# CDRon_wifi.net
KiCad netlist of a schematic drawn in Altium Designer
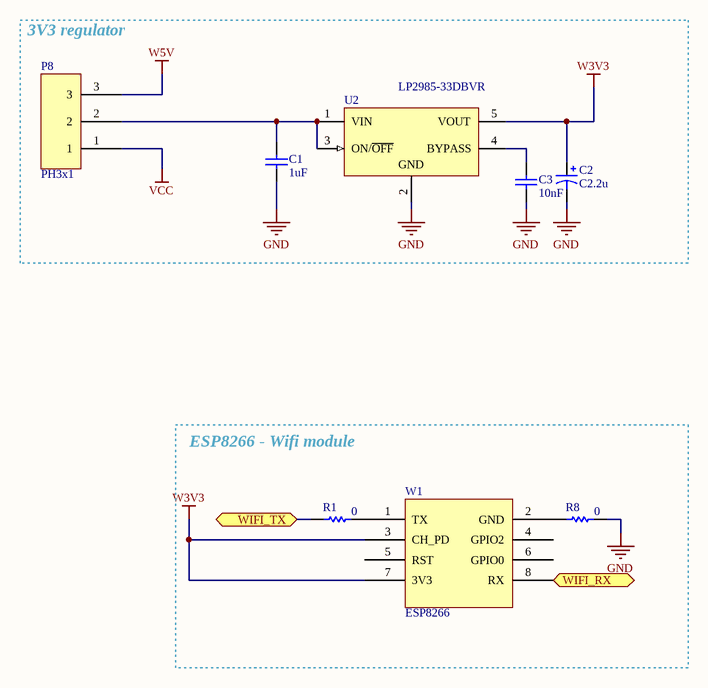
[diagram p0: CDRon_wifi.SchDoc]

(export (version "E")
  (design (tool "Eeschema 10.0.6"))
  (components
    (comp (ref "C1")
      (value "1uF")
      (footprint "0805")
      (description "Cap ceramic")
      (fields (field (name "Comment") "C1u"))
      (libsource (lib "CDRon_lib") (part "C"))
    )
    (comp (ref "C2")
      (value "C2.2u")
      (footprint "Tantalum")
      (description "Tantalum capacitor")
      (libsource (lib "CDRon_lib") (part "C Tantalum"))
    )
    (comp (ref "C3")
      (value "10nF")
      (footprint "C 1206")
      (description "Cap ceramic")
      (fields (field (name "Comment") "C10n"))
      (libsource (lib "CDRon_lib") (part "C"))
    )
    (comp (ref "P8") (value "PH3x1") (footprint "PH3x1") (libsource (lib "CDRon_lib") (part "PH3x1")))
    (comp (ref "R1")
      (value "0")
      (footprint "R 1206")
      (description "Resistencia")
      (fields (field (name ".CREATOR") "SR"))
      (libsource (lib "CDRon_lib") (part "R"))
    )
    (comp (ref "R8")
      (value "0")
      (footprint "R 1206")
      (description "Resistencia")
      (fields (field (name ".CREATOR") "SR"))
      (libsource (lib "CDRon_lib") (part "R"))
    )
    (comp (ref "U2")
      (value "LP2985-33DBVR")
      (footprint "TI-DBV5_N")
      (fields (field (name "MANUFACTURER") "Texas Instruments"))
      (libsource (lib "TI Power Management Linear Regulator Single Channel LDO (0-350mA)") (part "LP2985-10DBVR"))
    )
    (comp (ref "W1") (value "ESP8266") (footprint "ESP8266") (libsource (lib "CDRon_lib") (part "ESP8266")))
  )
  (nets
    (net (code "1") (name "/WIFI_RX") (class "Default")
      (node (ref "W1") (pin "8") (pinfunction "RX_8") (pintype "passive"))
    )
    (net (code "2") (name "/WIFI_TX") (class "Default")
      (node (ref "R1") (pin "1") (pinfunction "1_1") (pintype "passive"))
    )
    (net (code "3") (name "GND") (class "Default")
      (node (ref "C1") (pin "1") (pinfunction "1_1") (pintype "passive"))
      (node (ref "C2") (pin "2") (pinfunction "2_2") (pintype "passive"))
      (node (ref "C3") (pin "1") (pinfunction "1_1") (pintype "passive"))
      (node (ref "R8") (pin "2") (pinfunction "2_2") (pintype "passive"))
      (node (ref "U2") (pin "2") (pinfunction "GND_2") (pintype "power_in"))
    )
    (net (code "4") (name "Net-(U2-BYPASS)") (class "Default")
      (node (ref "C3") (pin "2") (pinfunction "2_2") (pintype "passive"))
      (node (ref "U2") (pin "4") (pinfunction "BYPASS_4") (pintype "passive"))
    )
    (net (code "5") (name "Net-(U2-ON{slash}~{OFF})") (class "Default")
      (node (ref "C1") (pin "2") (pinfunction "2_2") (pintype "passive"))
      (node (ref "P8") (pin "2") (pinfunction "2_2") (pintype "passive"))
      (node (ref "U2") (pin "1") (pinfunction "VIN_1") (pintype "power_in"))
      (node (ref "U2") (pin "3") (pinfunction "ON/~{OFF}_3") (pintype "input"))
    )
    (net (code "6") (name "Net-(W1-GND)") (class "Default")
      (node (ref "R8") (pin "1") (pinfunction "1_1") (pintype "passive"))
      (node (ref "W1") (pin "2") (pinfunction "GND_2") (pintype "passive"))
    )
    (net (code "7") (name "Net-(W1-TX)") (class "Default")
      (node (ref "R1") (pin "2") (pinfunction "2_2") (pintype "passive"))
      (node (ref "W1") (pin "1") (pinfunction "TX_1") (pintype "passive"))
    )
    (net (code "8") (name "VCC") (class "Default")
      (node (ref "P8") (pin "1") (pinfunction "1_1") (pintype "passive"))
    )
    (net (code "9") (name "W3V3") (class "Default")
      (node (ref "C2") (pin "1") (pinfunction "1_1") (pintype "passive"))
      (node (ref "U2") (pin "5") (pinfunction "VOUT_5") (pintype "power_in"))
      (node (ref "W1") (pin "3") (pinfunction "CH_PD_3") (pintype "passive"))
      (node (ref "W1") (pin "7") (pinfunction "3V3_7") (pintype "passive"))
    )
    (net (code "10") (name "W5V") (class "Default")
      (node (ref "P8") (pin "3") (pinfunction "3_3") (pintype "passive"))
    )
    (net (code "11") (name "unconnected-(W1-GPIO0-Pad6)") (class "Default")
      (node (ref "W1") (pin "6") (pinfunction "GPIO0_6") (pintype "passive"))
    )
    (net (code "12") (name "unconnected-(W1-GPIO2-Pad4)") (class "Default")
      (node (ref "W1") (pin "4") (pinfunction "GPIO2_4") (pintype "passive"))
    )
    (net (code "13") (name "unconnected-(W1-RST-Pad5)") (class "Default")
      (node (ref "W1") (pin "5") (pinfunction "RST_5") (pintype "passive"))
    )
  )
)
